# neoimage_sensors_small.net
KiCad netlist of a schematic drawn in EAGLE
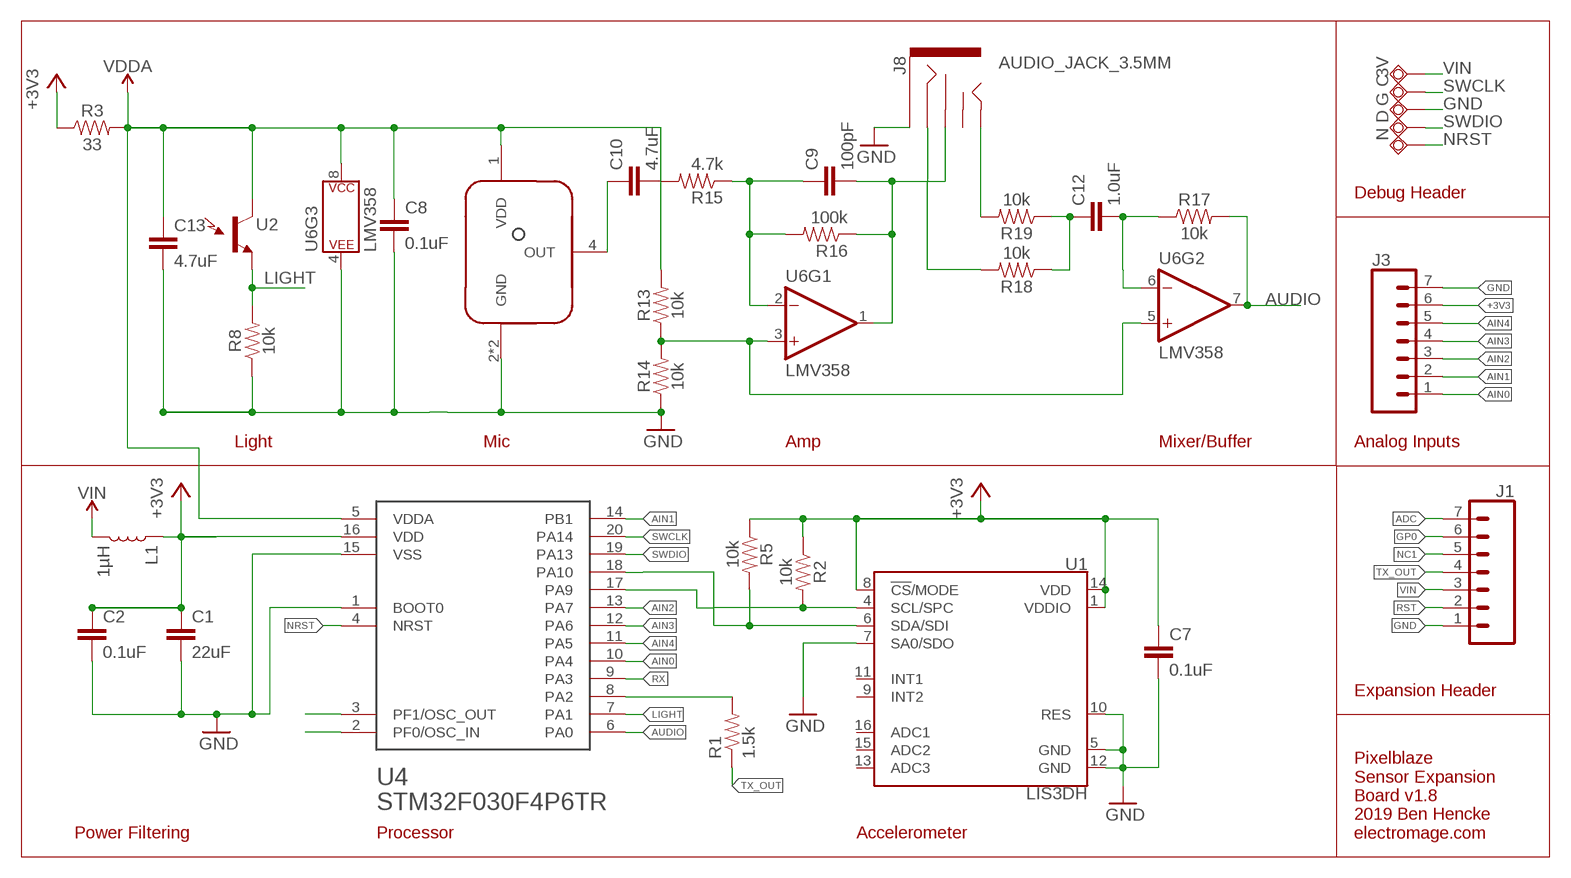
[diagram p0: schematic, sheet 1]

(export (version "E")
  (design (tool "Eeschema 10.0.6"))
  (components
    (comp (ref "3V")
      (value "TPSQTP18SQ")
      (footprint "eagle-import:TP18SQ")
      (libsource (lib "eagle-import") (part "TPSQTP18SQ"))
    )
    (comp (ref "C")
      (value "TPSQTP18SQ")
      (footprint "eagle-import:TP18SQ")
      (libsource (lib "eagle-import") (part "TPSQTP18SQ"))
    )
    (comp (ref "C1")
      (value "22uF")
      (footprint "eagle-import:0805")
      (libsource (lib "eagle-import") (part "22UF-0805-6.3V-20%"))
    )
    (comp (ref "C2")
      (value "0.1uF")
      (footprint "eagle-import:0603")
      (libsource (lib "eagle-import") (part "0.1UF-0603-25V-(+80/-20%)"))
    )
    (comp (ref "C7")
      (value "0.1uF")
      (footprint "eagle-import:0603")
      (libsource (lib "eagle-import") (part "0.1UF-0603-25V-(+80/-20%)"))
    )
    (comp (ref "C8")
      (value "0.1uF")
      (footprint "eagle-import:0603")
      (libsource (lib "eagle-import") (part "0.1UF-0603-25V-(+80/-20%)"))
    )
    (comp (ref "C9")
      (value "100pF")
      (footprint "eagle-import:0603")
      (libsource (lib "eagle-import") (part "100PF-0603-50V-5%"))
    )
    (comp (ref "C10")
      (value "4.7uF")
      (footprint "eagle-import:0603")
      (libsource (lib "eagle-import") (part "4.7UF0603"))
    )
    (comp (ref "C12")
      (value "1.0uF")
      (footprint "eagle-import:0603")
      (libsource (lib "eagle-import") (part "1.0UF-0603-16V-10%"))
    )
    (comp (ref "C13")
      (value "4.7uF")
      (footprint "eagle-import:0603")
      (libsource (lib "eagle-import") (part "4.7UF0603"))
    )
    (comp (ref "D")
      (value "TPSQTP18SQ")
      (footprint "eagle-import:TP18SQ")
      (libsource (lib "eagle-import") (part "TPSQTP18SQ"))
    )
    (comp (ref "G")
      (value "TPSQTP18SQ")
      (footprint "eagle-import:TP18SQ")
      (libsource (lib "eagle-import") (part "TPSQTP18SQ"))
    )
    (comp (ref "J1")
      (value "CONN_07LOCK")
      (footprint "eagle-import:1X07_LOCK")
      (libsource (lib "eagle-import") (part "CONN_07LOCK"))
    )
    (comp (ref "J3")
      (value "CONN_07LOCK")
      (footprint "eagle-import:1X07_LOCK")
      (libsource (lib "eagle-import") (part "SparkFun-Connectors_513_CONN_07LOCK"))
    )
    (comp (ref "J8")
      (value "AUDIO_JACK_3.5MM")
      (footprint "eagle-import:AUDIO-JACK-KIT")
      (libsource (lib "eagle-import") (part "AUDIO_JACK_3.5MM_KIT"))
    )
    (comp (ref "L1")
      (value "1µH")
      (footprint "eagle-import:0805")
      (libsource (lib "eagle-import") (part "INDUCTOR-0805-3.3UH"))
    )
    (comp (ref "N")
      (value "TPSQTP18SQ")
      (footprint "eagle-import:TP18SQ")
      (libsource (lib "eagle-import") (part "TPSQTP18SQ"))
    )
    (comp (ref "R1")
      (value "1.5k")
      (footprint "eagle-import:0603")
      (libsource (lib "eagle-import") (part "1.5KOHM-0603-1/10W-1%"))
    )
    (comp (ref "R2")
      (value "10k")
      (footprint "eagle-import:0603")
      (libsource (lib "eagle-import") (part "10KOHM-0603-1/10W-1%"))
    )
    (comp (ref "R3")
      (value "33")
      (footprint "eagle-import:0603")
      (libsource (lib "eagle-import") (part "33OHM-0603-1/10W-1%"))
    )
    (comp (ref "R5")
      (value "10k")
      (footprint "eagle-import:0603")
      (libsource (lib "eagle-import") (part "10KOHM-0603-1/10W-1%"))
    )
    (comp (ref "R8")
      (value "10k")
      (footprint "eagle-import:0603")
      (libsource (lib "eagle-import") (part "10KOHM-0603-1/10W-1%"))
    )
    (comp (ref "R13")
      (value "10k")
      (footprint "eagle-import:0603")
      (libsource (lib "eagle-import") (part "10KOHM-0603-1/10W-1%"))
    )
    (comp (ref "R14")
      (value "10k")
      (footprint "eagle-import:0603")
      (libsource (lib "eagle-import") (part "10KOHM-0603-1/10W-1%"))
    )
    (comp (ref "R15")
      (value "4.7k")
      (footprint "eagle-import:0603")
      (libsource (lib "eagle-import") (part "4.7KOHM-0603-1/10W-1%"))
    )
    (comp (ref "R16")
      (value "100k")
      (footprint "eagle-import:0603")
      (libsource (lib "eagle-import") (part "100KOHM-0603-1/10W-1%"))
    )
    (comp (ref "R17")
      (value "10k")
      (footprint "eagle-import:0603")
      (libsource (lib "eagle-import") (part "10KOHM-0603-1/10W-1%"))
    )
    (comp (ref "R18")
      (value "10k")
      (footprint "eagle-import:0603")
      (libsource (lib "eagle-import") (part "10KOHM-0603-1/10W-1%"))
    )
    (comp (ref "R19")
      (value "10k")
      (footprint "eagle-import:0603")
      (libsource (lib "eagle-import") (part "10KOHM-0603-1/10W-1%"))
    )
    (comp (ref "U$3")
      (value "MICROPHONE-MEMS")
      (footprint "eagle-import:MICROPHONE-MEMS-3X3.75")
      (libsource (lib "eagle-import") (part "MICROPHONE-MEMS"))
    )
    (comp (ref "U1")
      (value "LIS3DH")
      (footprint "eagle-import:LGA-16-3X3")
      (libsource (lib "eagle-import") (part "LIS3DH"))
    )
    (comp (ref "U2")
      (value "LIGHT_SENSORALS")
      (footprint "eagle-import:ALS-PT19")
      (libsource (lib "eagle-import") (part "LIGHT_SENSORALS"))
    )
    (comp (ref "U4")
      (value "STM32F030F4P6TR")
      (footprint "eagle-import:TSSOP-20")
      (libsource (lib "eagle-import") (part "STM32F030XTSSOP20"))
    )
    (comp (ref "U6")
      (value "LMV358")
      (footprint "eagle-import:SO08")
      (libsource (lib "eagle-import") (part "LMV358SOIC"))
    )
  )
  (nets
    (net (code "1") (name "+3V3") (class "Default")
      (node (ref "C1") (pin "1") (pinfunction "1_1") (pintype "passive"))
      (node (ref "C2") (pin "1") (pinfunction "1_1") (pintype "passive"))
      (node (ref "C7") (pin "1") (pinfunction "1_1") (pintype "passive"))
      (node (ref "J3") (pin "6") (pinfunction "6_6") (pintype "passive"))
      (node (ref "L1") (pin "1") (pinfunction "1_1") (pintype "passive"))
      (node (ref "R2") (pin "1") (pinfunction "1_1") (pintype "passive"))
      (node (ref "R3") (pin "1") (pinfunction "1_1") (pintype "passive"))
      (node (ref "R5") (pin "1") (pinfunction "1_1") (pintype "passive"))
      (node (ref "U1") (pin "1") (pinfunction "VDDIO_1") (pintype "bidirectional"))
      (node (ref "U1") (pin "14") (pinfunction "VDD_14") (pintype "bidirectional"))
      (node (ref "U1") (pin "8") (pinfunction "~{CS}/MODE_8") (pintype "bidirectional"))
      (node (ref "U4") (pin "16") (pinfunction "VDD_16") (pintype "bidirectional"))
    )
    (net (code "2") (name "ADC") (class "Default")
      (node (ref "J1") (pin "7") (pinfunction "7_7") (pintype "passive"))
    )
    (net (code "3") (name "AIN0") (class "Default")
      (node (ref "J3") (pin "1") (pinfunction "1_1") (pintype "passive"))
      (node (ref "U4") (pin "10") (pinfunction "PA4_10") (pintype "bidirectional"))
    )
    (net (code "4") (name "AIN1") (class "Default")
      (node (ref "J3") (pin "2") (pinfunction "2_2") (pintype "passive"))
      (node (ref "U4") (pin "14") (pinfunction "PB1_14") (pintype "bidirectional"))
    )
    (net (code "5") (name "AIN2") (class "Default")
      (node (ref "J3") (pin "3") (pinfunction "3_3") (pintype "passive"))
      (node (ref "U4") (pin "13") (pinfunction "PA7_13") (pintype "bidirectional"))
    )
    (net (code "6") (name "AIN3") (class "Default")
      (node (ref "J3") (pin "4") (pinfunction "4_4") (pintype "passive"))
      (node (ref "U4") (pin "12") (pinfunction "PA6_12") (pintype "bidirectional"))
    )
    (net (code "7") (name "AIN4") (class "Default")
      (node (ref "J3") (pin "5") (pinfunction "5_5") (pintype "passive"))
      (node (ref "U4") (pin "11") (pinfunction "PA5_11") (pintype "bidirectional"))
    )
    (net (code "8") (name "AUDIO") (class "Default")
      (node (ref "R17") (pin "2") (pinfunction "2_2") (pintype "passive"))
      (node (ref "U4") (pin "6") (pinfunction "PA0_6") (pintype "bidirectional"))
      (node (ref "U6") (pin "7") (pinfunction "OUT_7") (pintype "output"))
    )
    (net (code "9") (name "GND") (class "Default")
      (node (ref "C1") (pin "2") (pinfunction "2_2") (pintype "passive"))
      (node (ref "C13") (pin "2") (pinfunction "2_2") (pintype "passive"))
      (node (ref "C2") (pin "2") (pinfunction "2_2") (pintype "passive"))
      (node (ref "C7") (pin "2") (pinfunction "2_2") (pintype "passive"))
      (node (ref "C8") (pin "2") (pinfunction "2_2") (pintype "passive"))
      (node (ref "G") (pin "TP") (pinfunction "TP_TP") (pintype "input"))
      (node (ref "J1") (pin "1") (pinfunction "1_1") (pintype "passive"))
      (node (ref "J3") (pin "7") (pinfunction "7_7") (pintype "passive"))
      (node (ref "J8") (pin "SLEEVE") (pinfunction "SLEEVE_SLEEVE") (pintype "bidirectional"))
      (node (ref "R14") (pin "1") (pinfunction "1_1") (pintype "passive"))
      (node (ref "R8") (pin "1") (pinfunction "1_1") (pintype "passive"))
      (node (ref "U$3") (pin "2") (pinfunction "GND_2") (pintype "bidirectional"))
      (node (ref "U$3") (pin "3") (pinfunction "GND_3") (pintype "bidirectional"))
      (node (ref "U1") (pin "10") (pinfunction "RES_10") (pintype "bidirectional"))
      (node (ref "U1") (pin "12") (pinfunction "GND_12") (pintype "bidirectional"))
      (node (ref "U1") (pin "5") (pinfunction "GND_5") (pintype "bidirectional"))
      (node (ref "U1") (pin "7") (pinfunction "SA0/SDO_7") (pintype "bidirectional"))
      (node (ref "U4") (pin "1") (pinfunction "BOOT0_1") (pintype "bidirectional"))
      (node (ref "U4") (pin "15") (pinfunction "VSS_15") (pintype "bidirectional"))
      (node (ref "U6") (pin "4") (pinfunction "P$V-_4") (pintype "bidirectional"))
    )
    (net (code "10") (name "GP0") (class "Default")
      (node (ref "J1") (pin "6") (pinfunction "6_6") (pintype "passive"))
    )
    (net (code "11") (name "LIGHT") (class "Default")
      (node (ref "R8") (pin "2") (pinfunction "2_2") (pintype "passive"))
      (node (ref "U2") (pin "E") (pinfunction "E1_E") (pintype "passive"))
      (node (ref "U4") (pin "7") (pinfunction "PA1_7") (pintype "bidirectional"))
    )
    (net (code "12") (name "NC1") (class "Default")
      (node (ref "J1") (pin "5") (pinfunction "5_5") (pintype "passive"))
    )
    (net (code "13") (name "NRST") (class "Default")
      (node (ref "N") (pin "TP") (pinfunction "TP_TP") (pintype "input"))
      (node (ref "U4") (pin "4") (pinfunction "NRST_4") (pintype "bidirectional"))
    )
    (net (code "14") (name "Net-(C10-Pad2)") (class "Default")
      (node (ref "C10") (pin "2") (pinfunction "2_2") (pintype "passive"))
      (node (ref "R15") (pin "2") (pinfunction "2_2") (pintype "passive"))
    )
    (net (code "15") (name "Net-(C12-Pad1)") (class "Default")
      (node (ref "C12") (pin "1") (pinfunction "1_1") (pintype "passive"))
      (node (ref "R18") (pin "1") (pinfunction "1_1") (pintype "passive"))
      (node (ref "R19") (pin "1") (pinfunction "1_1") (pintype "passive"))
    )
    (net (code "16") (name "Net-(J8-PadRING)") (class "Default")
      (node (ref "J8") (pin "RING") (pinfunction "RING_RING") (pintype "bidirectional"))
      (node (ref "R18") (pin "2") (pinfunction "2_2") (pintype "passive"))
    )
    (net (code "17") (name "Net-(J8-PadTIP)") (class "Default")
      (node (ref "J8") (pin "TIP") (pinfunction "TIP_TIP") (pintype "bidirectional"))
      (node (ref "R19") (pin "2") (pinfunction "2_2") (pintype "passive"))
    )
    (net (code "18") (name "Net-(U$3-OUT)") (class "Default")
      (node (ref "C10") (pin "1") (pinfunction "1_1") (pintype "passive"))
      (node (ref "U$3") (pin "4") (pinfunction "OUT_4") (pintype "bidirectional"))
    )
    (net (code "19") (name "Net-(U1-SCL{slash}SPC)") (class "Default")
      (node (ref "R2") (pin "2") (pinfunction "2_2") (pintype "passive"))
      (node (ref "U1") (pin "4") (pinfunction "SCL/SPC_4") (pintype "bidirectional"))
      (node (ref "U4") (pin "17") (pinfunction "PA9_17") (pintype "bidirectional"))
    )
    (net (code "20") (name "Net-(U1-SDA{slash}SDI)") (class "Default")
      (node (ref "R5") (pin "2") (pinfunction "2_2") (pintype "passive"))
      (node (ref "U1") (pin "6") (pinfunction "SDA/SDI_6") (pintype "bidirectional"))
      (node (ref "U4") (pin "18") (pinfunction "PA10_18") (pintype "bidirectional"))
    )
    (net (code "21") (name "Net-(U4-PA2)") (class "Default")
      (node (ref "R1") (pin "2") (pinfunction "2_2") (pintype "passive"))
      (node (ref "U4") (pin "8") (pinfunction "PA2_8") (pintype "bidirectional"))
    )
    (net (code "22") (name "Net-(U6A-+IN)") (class "Default")
      (node (ref "R13") (pin "1") (pinfunction "1_1") (pintype "passive"))
      (node (ref "R14") (pin "2") (pinfunction "2_2") (pintype "passive"))
      (node (ref "U6") (pin "3") (pinfunction "+IN_3") (pintype "input"))
      (node (ref "U6") (pin "5") (pinfunction "+IN_5") (pintype "input"))
    )
    (net (code "23") (name "Net-(U6A--IN)") (class "Default")
      (node (ref "C9") (pin "1") (pinfunction "1_1") (pintype "passive"))
      (node (ref "R15") (pin "1") (pinfunction "1_1") (pintype "passive"))
      (node (ref "R16") (pin "2") (pinfunction "2_2") (pintype "passive"))
      (node (ref "U6") (pin "2") (pinfunction "-IN_2") (pintype "input"))
    )
    (net (code "24") (name "Net-(U6A-OUT)") (class "Default")
      (node (ref "C9") (pin "2") (pinfunction "2_2") (pintype "passive"))
      (node (ref "J8") (pin "RSH") (pinfunction "RSH_RSH") (pintype "bidirectional"))
      (node (ref "R16") (pin "1") (pinfunction "1_1") (pintype "passive"))
      (node (ref "U6") (pin "1") (pinfunction "OUT_1") (pintype "output"))
    )
    (net (code "25") (name "Net-(U6B--IN)") (class "Default")
      (node (ref "C12") (pin "2") (pinfunction "2_2") (pintype "passive"))
      (node (ref "R17") (pin "1") (pinfunction "1_1") (pintype "passive"))
      (node (ref "U6") (pin "6") (pinfunction "-IN_6") (pintype "input"))
    )
    (net (code "26") (name "RST") (class "Default")
      (node (ref "J1") (pin "2") (pinfunction "2_2") (pintype "passive"))
    )
    (net (code "27") (name "RX") (class "Default")
      (node (ref "U4") (pin "9") (pinfunction "PA3_9") (pintype "bidirectional"))
    )
    (net (code "28") (name "SWCLK") (class "Default")
      (node (ref "C") (pin "TP") (pinfunction "TP_TP") (pintype "input"))
      (node (ref "U4") (pin "20") (pinfunction "PA14_20") (pintype "bidirectional"))
    )
    (net (code "29") (name "SWDIO") (class "Default")
      (node (ref "D") (pin "TP") (pinfunction "TP_TP") (pintype "input"))
      (node (ref "U4") (pin "19") (pinfunction "PA13_19") (pintype "bidirectional"))
    )
    (net (code "30") (name "TX_OUT") (class "Default")
      (node (ref "J1") (pin "4") (pinfunction "4_4") (pintype "passive"))
      (node (ref "R1") (pin "1") (pinfunction "1_1") (pintype "passive"))
    )
    (net (code "31") (name "VDDA") (class "Default")
      (node (ref "C13") (pin "1") (pinfunction "1_1") (pintype "passive"))
      (node (ref "C8") (pin "1") (pinfunction "1_1") (pintype "passive"))
      (node (ref "R13") (pin "2") (pinfunction "2_2") (pintype "passive"))
      (node (ref "R3") (pin "2") (pinfunction "2_2") (pintype "passive"))
      (node (ref "U$3") (pin "1") (pinfunction "VDD_1") (pintype "bidirectional"))
      (node (ref "U2") (pin "C") (pinfunction "C1_C") (pintype "passive"))
      (node (ref "U4") (pin "5") (pinfunction "VDDA_5") (pintype "bidirectional"))
      (node (ref "U6") (pin "8") (pinfunction "P$V+_8") (pintype "bidirectional"))
    )
    (net (code "32") (name "VIN") (class "Default")
      (node (ref "3V") (pin "TP") (pinfunction "TP_TP") (pintype "input"))
      (node (ref "J1") (pin "3") (pinfunction "3_3") (pintype "passive"))
      (node (ref "L1") (pin "2") (pinfunction "2_2") (pintype "passive"))
    )
    (net (code "33") (name "unconnected-(J8-PadTSH)") (class "Default")
      (node (ref "J8") (pin "TSH") (pinfunction "TSH_TSH") (pintype "bidirectional"))
    )
    (net (code "34") (name "unconnected-(U1-ADC1-Pad16)") (class "Default")
      (node (ref "U1") (pin "16") (pinfunction "ADC1_16") (pintype "bidirectional"))
    )
    (net (code "35") (name "unconnected-(U1-ADC2-Pad15)") (class "Default")
      (node (ref "U1") (pin "15") (pinfunction "ADC2_15") (pintype "bidirectional"))
    )
    (net (code "36") (name "unconnected-(U1-ADC3-Pad13)") (class "Default")
      (node (ref "U1") (pin "13") (pinfunction "ADC3_13") (pintype "bidirectional"))
    )
    (net (code "37") (name "unconnected-(U1-INT1-Pad11)") (class "Default")
      (node (ref "U1") (pin "11") (pinfunction "INT1_11") (pintype "bidirectional"))
    )
    (net (code "38") (name "unconnected-(U1-INT2-Pad9)") (class "Default")
      (node (ref "U1") (pin "9") (pinfunction "INT2_9") (pintype "bidirectional"))
    )
    (net (code "39") (name "unconnected-(U4-PF0{slash}OSC_IN-Pad2)") (class "Default")
      (node (ref "U4") (pin "2") (pinfunction "PF0/OSC_IN_2") (pintype "bidirectional"))
    )
    (net (code "40") (name "unconnected-(U4-PF1{slash}OSC_OUT-Pad3)") (class "Default")
      (node (ref "U4") (pin "3") (pinfunction "PF1/OSC_OUT_3") (pintype "bidirectional"))
    )
  )
)
